# CAN.net
KiCad netlist of a schematic drawn in Altium Designer
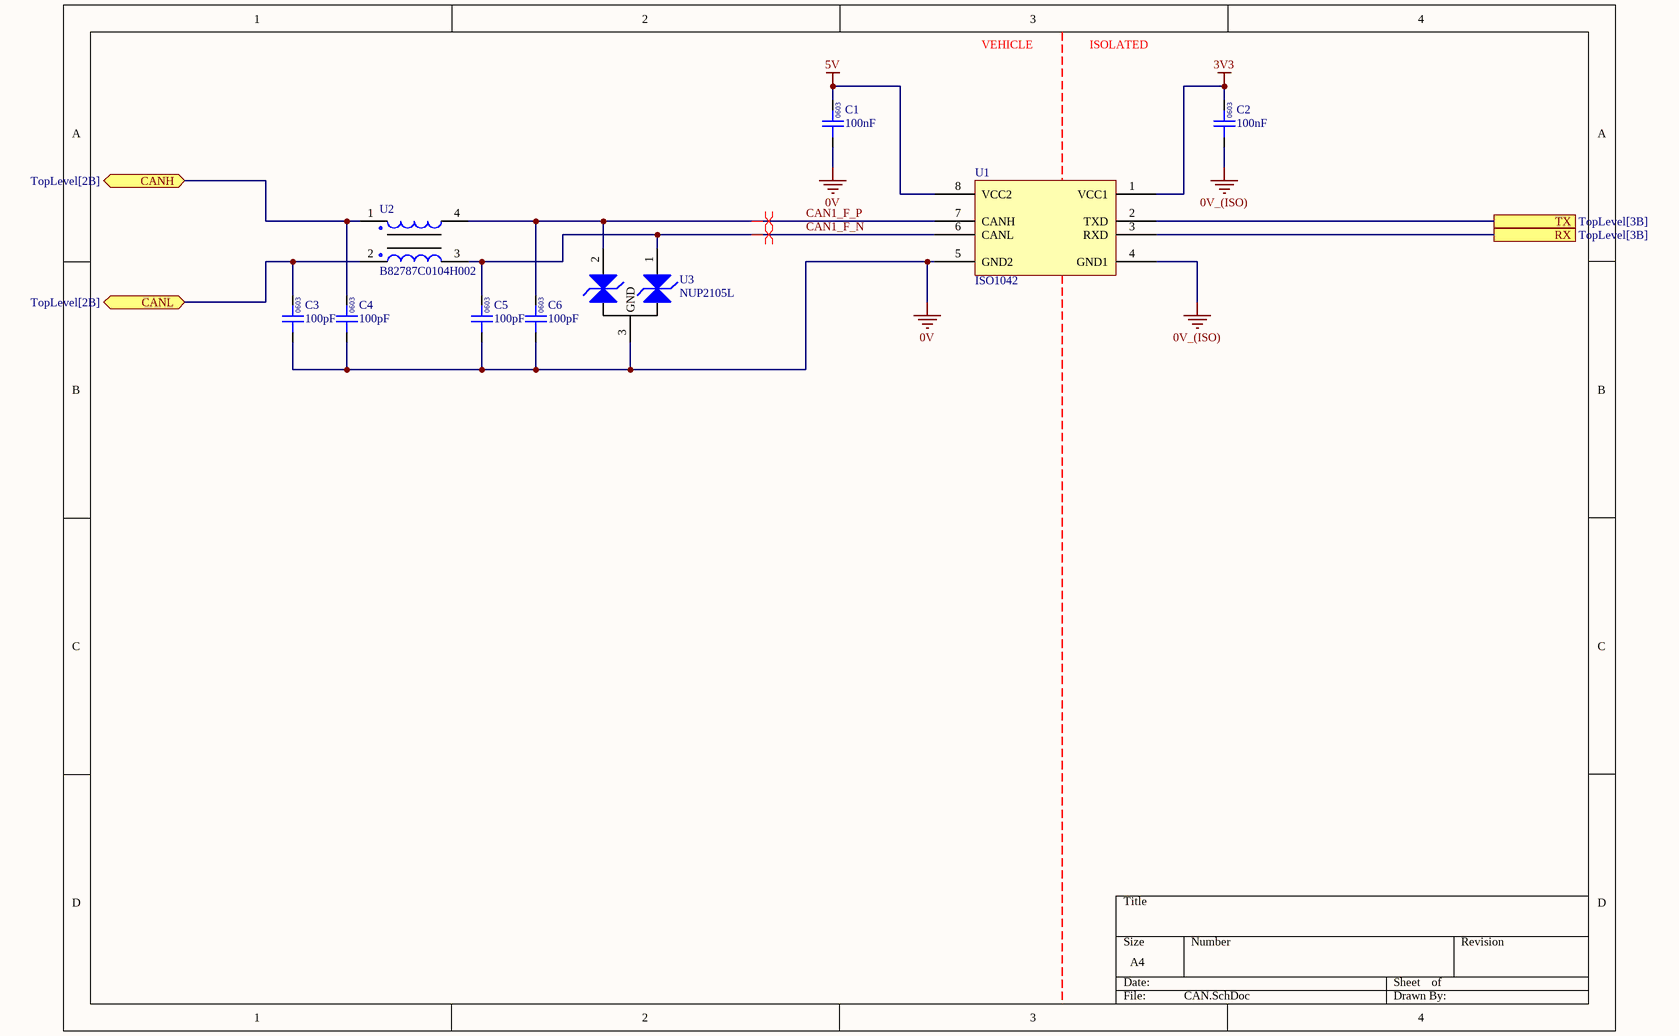
[diagram p0: CAN.SchDoc]

(export (version "E")
  (design (tool "Eeschema 10.0.6"))
  (components
    (comp (ref "C1")
      (value "100nF")
      (footprint "0603")
      (fields
        (field (name "PART NUMBER") "GCM188L81H104KA57D")
        (field (name "MANUFACTURER") "muRata")
        (field (name "TOLERANCE") "±10%")
      )
      (libsource (lib "ts_standard_library") (part "Capacitor 0603"))
    )
    (comp (ref "C2")
      (value "100nF")
      (footprint "0603")
      (fields
        (field (name "PART NUMBER") "GCM188L81H104KA57D")
        (field (name "MANUFACTURER") "muRata")
        (field (name "TOLERANCE") "±10%")
      )
      (libsource (lib "ts_standard_library") (part "Capacitor 0603"))
    )
    (comp (ref "C3")
      (value "100pF")
      (footprint "0603")
      (fields
        (field (name "PART NUMBER") "GRM1885C1H101JA01D")
        (field (name "MANUFACTURER") "Murata Electronics")
        (field (name "TOLERANCE") "±5%")
      )
      (libsource (lib "ts_standard_library") (part "Capacitor 0603"))
    )
    (comp (ref "C4")
      (value "100pF")
      (footprint "0603")
      (fields
        (field (name "PART NUMBER") "GRM1885C1H101JA01D")
        (field (name "MANUFACTURER") "Murata Electronics")
        (field (name "TOLERANCE") "±5%")
      )
      (libsource (lib "ts_standard_library") (part "Capacitor 0603"))
    )
    (comp (ref "C5")
      (value "100pF")
      (footprint "0603")
      (fields
        (field (name "PART NUMBER") "GRM1885C1H101JA01D")
        (field (name "MANUFACTURER") "Murata Electronics")
        (field (name "TOLERANCE") "±5%")
      )
      (libsource (lib "ts_standard_library") (part "Capacitor 0603"))
    )
    (comp (ref "C6")
      (value "100pF")
      (footprint "0603")
      (fields
        (field (name "PART NUMBER") "GRM1885C1H101JA01D")
        (field (name "MANUFACTURER") "Murata Electronics")
        (field (name "TOLERANCE") "±5%")
      )
      (libsource (lib "ts_standard_library") (part "Capacitor 0603"))
    )
    (comp (ref "U1")
      (value "ISO1042")
      (footprint "TI-SOIC-8")
      (description "IC CAN TRANSCEIVER 1/1 8SOIC")
      (fields
        (field (name "MANUFACTURER") "Texas Instruments")
        (field (name "DIGIKEY PART NUMBER") "296-ISO1042BQDWVQ1-ND")
      )
      (libsource (lib "ts_standard_library") (part "ISO1042"))
    )
    (comp (ref "U2")
      (value "B82787C0104H002")
      (footprint "TDK 4-PC Pad")
      (fields
        (field (name "MANUFACTURER") "EPCOS (TDK)")
        (field (name "DIGIKEY PART NUMBER") "495-4598-1-ND")
      )
      (libsource (lib "ts_standard_library") (part "B82787C0104H002"))
    )
    (comp (ref "U3")
      (value "NUP2105L")
      (footprint "ON SOT-23")
      (description "Dual Line CAN Bus Protector")
      (fields
        (field (name "MANUFACTURER") "ON Semiconductor")
        (field (name "DIGIKEY PART NUMBER") "NUP2105LT1GOSCT-ND")
      )
      (libsource (lib "ts_standard_library") (part "NUP2105L"))
    )
  )
  (nets
    (net (code "1") (name "/CAN1_F_N") (class "Default")
      (node (ref "C5") (pin "2") (pinfunction "2_2") (pintype "passive"))
      (node (ref "U1") (pin "6") (pinfunction "CANL_6") (pintype "passive"))
      (node (ref "U2") (pin "3") (pinfunction "3_3") (pintype "passive"))
      (node (ref "U3") (pin "1") (pinfunction "CAN_H_1") (pintype "passive"))
    )
    (net (code "2") (name "/CAN1_F_P") (class "Default")
      (node (ref "C6") (pin "2") (pinfunction "2_2") (pintype "passive"))
      (node (ref "U1") (pin "7") (pinfunction "CANH_7") (pintype "passive"))
      (node (ref "U2") (pin "4") (pinfunction "4_4") (pintype "passive"))
      (node (ref "U3") (pin "2") (pinfunction "CAN_L_2") (pintype "passive"))
    )
    (net (code "3") (name "/CANH") (class "Default")
      (node (ref "C4") (pin "2") (pinfunction "2_2") (pintype "passive"))
      (node (ref "U2") (pin "1") (pinfunction "1_1") (pintype "passive"))
    )
    (net (code "4") (name "/CANL") (class "Default")
      (node (ref "C3") (pin "2") (pinfunction "2_2") (pintype "passive"))
      (node (ref "U2") (pin "2") (pinfunction "2_2") (pintype "passive"))
    )
    (net (code "5") (name "/RX") (class "Default")
      (node (ref "U1") (pin "3") (pinfunction "RXD_3") (pintype "passive"))
    )
    (net (code "6") (name "/TX") (class "Default")
      (node (ref "U1") (pin "2") (pinfunction "TXD_2") (pintype "passive"))
    )
    (net (code "7") (name "0V") (class "Default")
      (node (ref "C1") (pin "1") (pinfunction "1_1") (pintype "passive"))
      (node (ref "C3") (pin "1") (pinfunction "1_1") (pintype "passive"))
      (node (ref "C4") (pin "1") (pinfunction "1_1") (pintype "passive"))
      (node (ref "C5") (pin "1") (pinfunction "1_1") (pintype "passive"))
      (node (ref "C6") (pin "1") (pinfunction "1_1") (pintype "passive"))
      (node (ref "U1") (pin "5") (pinfunction "GND2_5") (pintype "passive"))
      (node (ref "U3") (pin "3") (pinfunction "GND_3") (pintype "passive"))
    )
    (net (code "8") (name "0V_(ISO)") (class "Default")
      (node (ref "C2") (pin "1") (pinfunction "1_1") (pintype "passive"))
      (node (ref "U1") (pin "4") (pinfunction "GND1_4") (pintype "passive"))
    )
    (net (code "9") (name "3V3") (class "Default")
      (node (ref "C2") (pin "2") (pinfunction "2_2") (pintype "passive"))
      (node (ref "U1") (pin "1") (pinfunction "VCC1_1") (pintype "passive"))
    )
    (net (code "10") (name "5V") (class "Default")
      (node (ref "C1") (pin "2") (pinfunction "2_2") (pintype "passive"))
      (node (ref "U1") (pin "8") (pinfunction "VCC2_8") (pintype "passive"))
    )
  )
)
